# 12_FPGA_banks_3A_3B_4A.net
KiCad netlist of a schematic drawn in Altium Designer
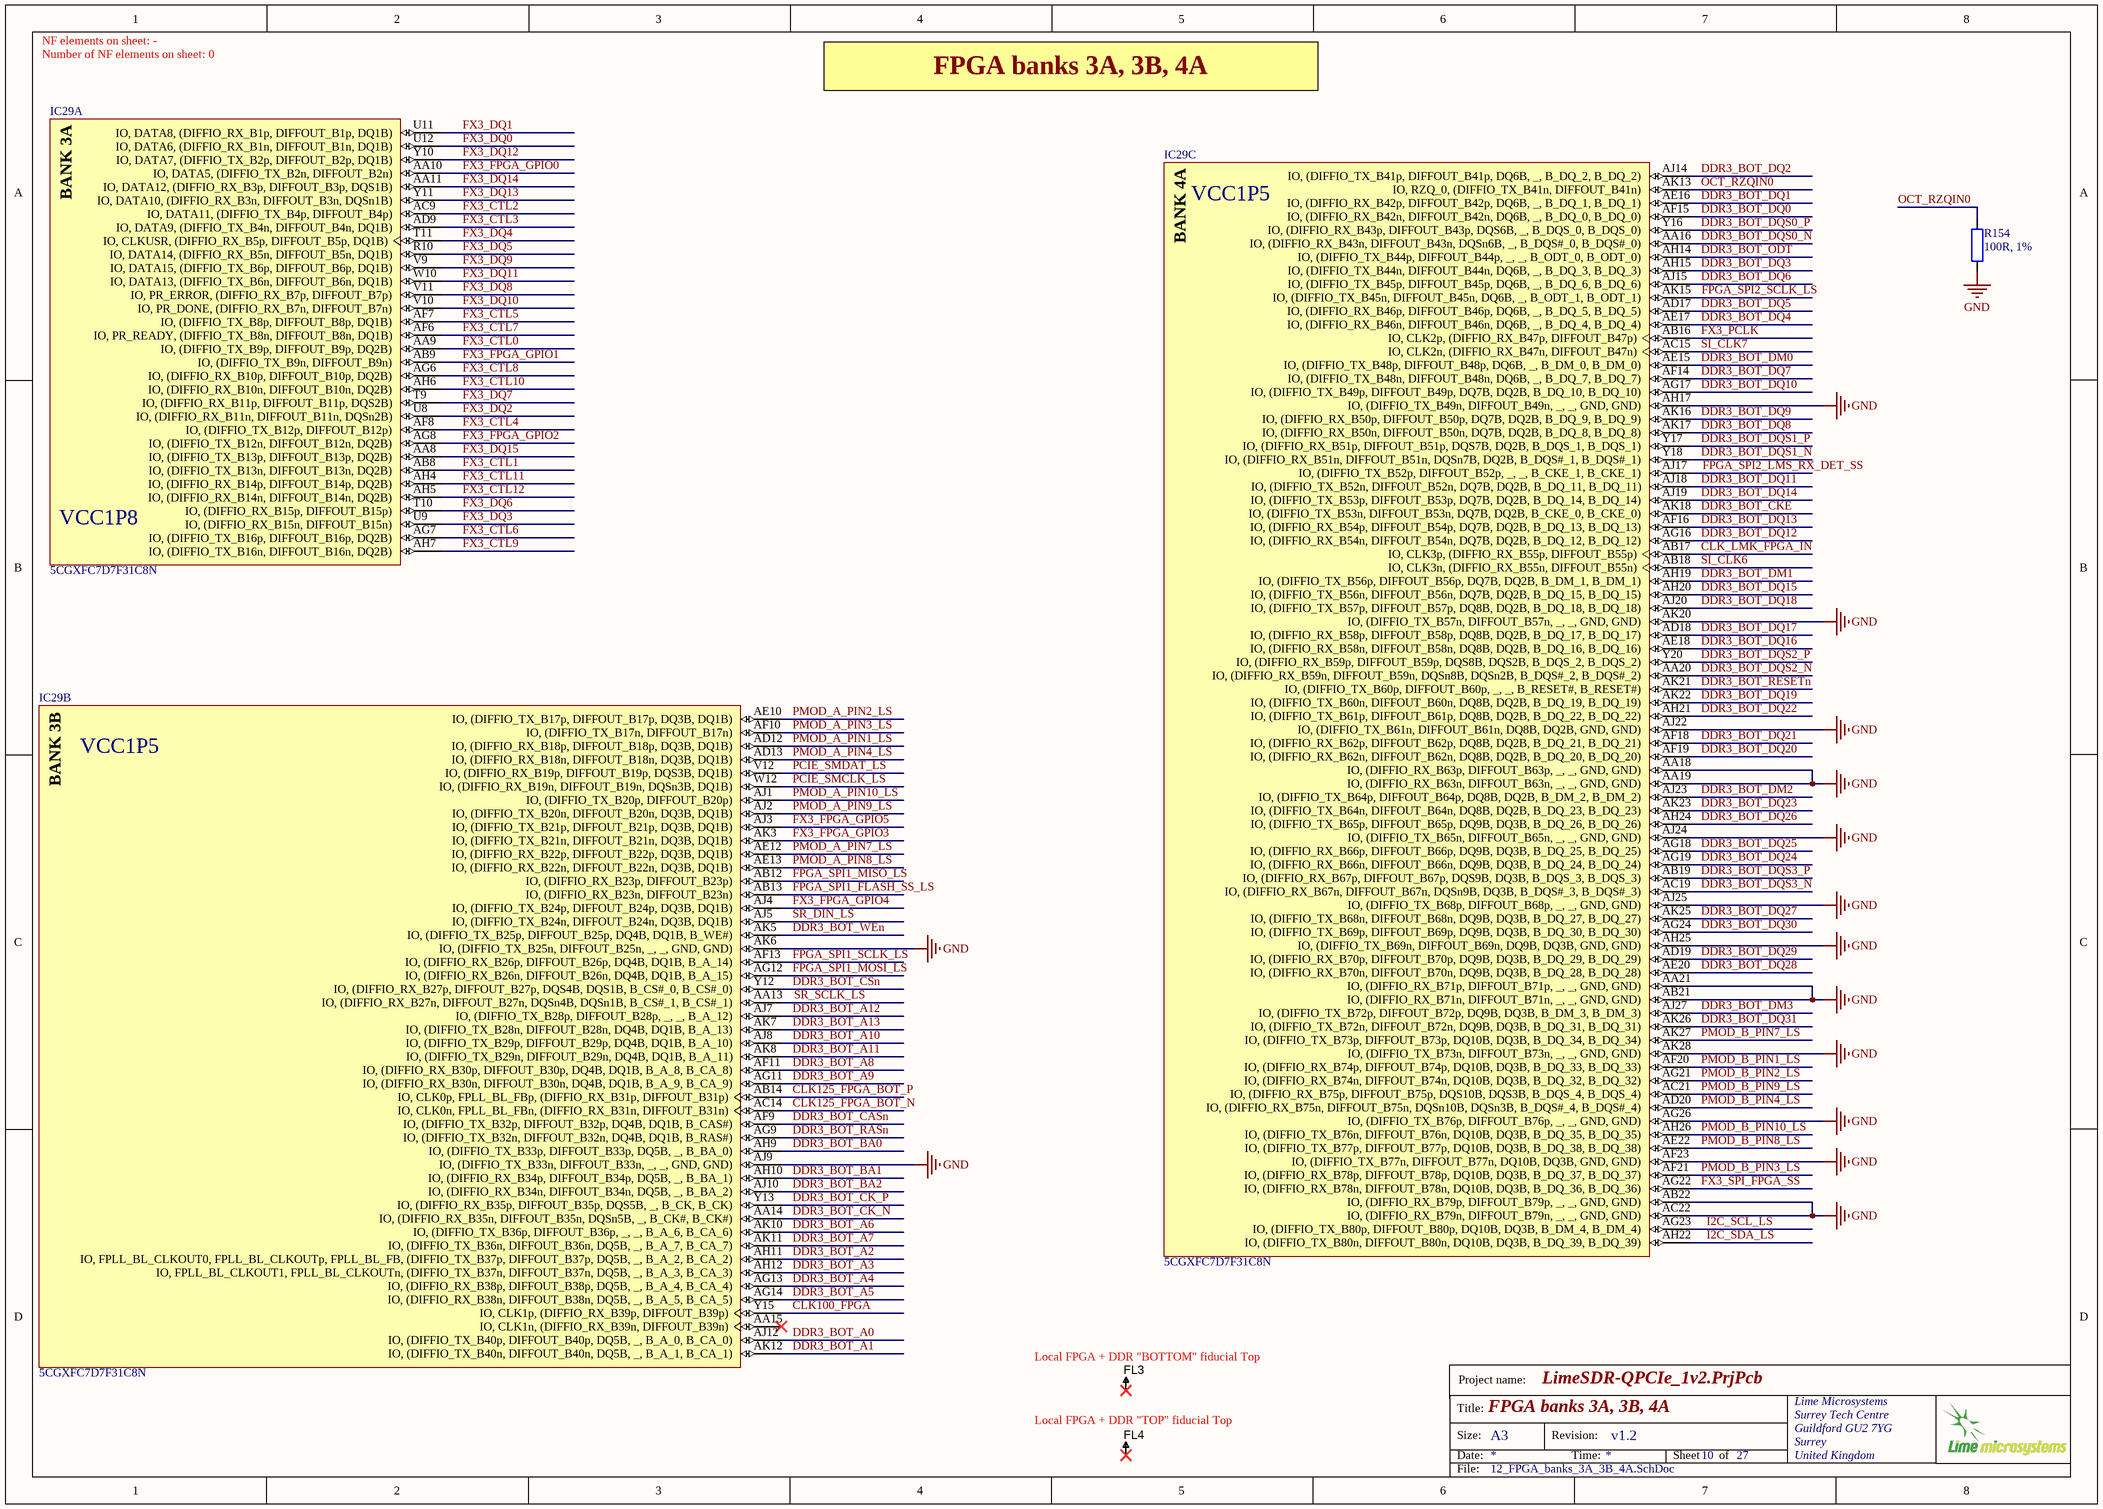
[diagram p0: 12_FPGA_banks_3A_3B_4A.SchDoc]

(export (version "E")
  (design (tool "Eeschema 10.0.6"))
  (components
    (comp (ref "FL3")
      (value "Fiducial")
      (footprint "Fiducial_local")
      (libsource (lib "LimeMicroAltiumLib_schLib") (part "Fiducial"))
    )
    (comp (ref "FL4")
      (value "Fiducial")
      (footprint "Fiducial_local")
      (libsource (lib "LimeMicroAltiumLib_schLib") (part "Fiducial"))
    )
    (comp (ref "IC29")
      (value "5CGXFC7D7F31C8N")
      (footprint "ALTR-FBGA896_A-200")
      (fields (field (name "MANUFACTURER") "Altera"))
      (libsource (lib "LimeMicroAltiumLib_schLib") (part "5CGXFC7D7F31C8N"))
    )
    (comp (ref "R154")
      (value "100R, 1%")
      (footprint "RES0402")
      (fields (field (name "TOLERANCE") "±1%") (field (name "MANUFACTURER") "Stackpole Electronics Inc."))
      (libsource (lib "LimeFPGAboard_schLib") (part "Res_0402"))
    )
  )
  (nets
    (net (code "1") (name "/CLK100_FPGA") (class "Default")
      (node (ref "IC29") (pin "Y15") (pinfunction "IO,_CLK1p,_(DIFFIO_RX_B39p,_DIFFOUT_B39p)_Y15") (pintype "bidirectional"))
    )
    (net (code "2") (name "/CLK125_FPGA_BOT_N") (class "Default")
      (node (ref "IC29") (pin "AC14") (pinfunction "IO,_CLK0n,_FPLL_BL_FBn,_(DIFFIO_RX_B31n,_DIFFOUT_B31n)_AC14") (pintype "bidirectional"))
    )
    (net (code "3") (name "/CLK125_FPGA_BOT_P") (class "Default")
      (node (ref "IC29") (pin "AB14") (pinfunction "IO,_CLK0p,_FPLL_BL_FBp,_(DIFFIO_RX_B31p,_DIFFOUT_B31p)_AB14") (pintype "bidirectional"))
    )
    (net (code "4") (name "/CLK_LMK_FPGA_IN") (class "Default")
      (node (ref "IC29") (pin "AB17") (pinfunction "IO,_CLK3p,_(DIFFIO_RX_B55p,_DIFFOUT_B55p)_AB17") (pintype "bidirectional"))
    )
    (net (code "5") (name "/DDR3_BOT_A0") (class "Default")
      (node (ref "IC29") (pin "AJ12") (pinfunction "IO,_(DIFFIO_TX_B40p,_DIFFOUT_B40p,_DQ5B,__,_B_A_0,_B_CA_0)_AJ12") (pintype "bidirectional"))
    )
    (net (code "6") (name "/DDR3_BOT_A1") (class "Default")
      (node (ref "IC29") (pin "AK12") (pinfunction "IO,_(DIFFIO_TX_B40n,_DIFFOUT_B40n,_DQ5B,__,_B_A_1,_B_CA_1)_AK12") (pintype "bidirectional"))
    )
    (net (code "7") (name "/DDR3_BOT_A2") (class "Default")
      (node (ref "IC29") (pin "AH11") (pinfunction "IO,_FPLL_BL_CLKOUT0,_FPLL_BL_CLKOUTp,_FPLL_BL_FB,_(DIFFIO_TX_B37p,_DIFFOUT_B37p,_DQ5B,__,_B_A_2,_B_CA_2)_AH11") (pintype "bidirectional"))
    )
    (net (code "8") (name "/DDR3_BOT_A3") (class "Default")
      (node (ref "IC29") (pin "AH12") (pinfunction "IO,_FPLL_BL_CLKOUT1,_FPLL_BL_CLKOUTn,_(DIFFIO_TX_B37n,_DIFFOUT_B37n,_DQ5B,__,_B_A_3,_B_CA_3)_AH12") (pintype "bidirectional"))
    )
    (net (code "9") (name "/DDR3_BOT_A4") (class "Default")
      (node (ref "IC29") (pin "AG13") (pinfunction "IO,_(DIFFIO_RX_B38p,_DIFFOUT_B38p,_DQ5B,__,_B_A_4,_B_CA_4)_AG13") (pintype "bidirectional"))
    )
    (net (code "10") (name "/DDR3_BOT_A5") (class "Default")
      (node (ref "IC29") (pin "AG14") (pinfunction "IO,_(DIFFIO_RX_B38n,_DIFFOUT_B38n,_DQ5B,__,_B_A_5,_B_CA_5)_AG14") (pintype "bidirectional"))
    )
    (net (code "11") (name "/DDR3_BOT_A6") (class "Default")
      (node (ref "IC29") (pin "AK10") (pinfunction "IO,_(DIFFIO_TX_B36p,_DIFFOUT_B36p,__,__,_B_A_6,_B_CA_6)_AK10") (pintype "bidirectional"))
    )
    (net (code "12") (name "/DDR3_BOT_A7") (class "Default")
      (node (ref "IC29") (pin "AK11") (pinfunction "IO,_(DIFFIO_TX_B36n,_DIFFOUT_B36n,_DQ5B,__,_B_A_7,_B_CA_7)_AK11") (pintype "bidirectional"))
    )
    (net (code "13") (name "/DDR3_BOT_A8") (class "Default")
      (node (ref "IC29") (pin "AF11") (pinfunction "IO,_(DIFFIO_RX_B30p,_DIFFOUT_B30p,_DQ4B,_DQ1B,_B_A_8,_B_CA_8)_AF11") (pintype "bidirectional"))
    )
    (net (code "14") (name "/DDR3_BOT_A9") (class "Default")
      (node (ref "IC29") (pin "AG11") (pinfunction "IO,_(DIFFIO_RX_B30n,_DIFFOUT_B30n,_DQ4B,_DQ1B,_B_A_9,_B_CA_9)_AG11") (pintype "bidirectional"))
    )
    (net (code "15") (name "/DDR3_BOT_A10") (class "Default")
      (node (ref "IC29") (pin "AJ8") (pinfunction "IO,_(DIFFIO_TX_B29p,_DIFFOUT_B29p,_DQ4B,_DQ1B,_B_A_10)_AJ8") (pintype "bidirectional"))
    )
    (net (code "16") (name "/DDR3_BOT_A11") (class "Default")
      (node (ref "IC29") (pin "AK8") (pinfunction "IO,_(DIFFIO_TX_B29n,_DIFFOUT_B29n,_DQ4B,_DQ1B,_B_A_11)_AK8") (pintype "bidirectional"))
    )
    (net (code "17") (name "/DDR3_BOT_A12") (class "Default")
      (node (ref "IC29") (pin "AJ7") (pinfunction "IO,_(DIFFIO_TX_B28p,_DIFFOUT_B28p,__,__,_B_A_12)_AJ7") (pintype "bidirectional"))
    )
    (net (code "18") (name "/DDR3_BOT_A13") (class "Default")
      (node (ref "IC29") (pin "AK7") (pinfunction "IO,_(DIFFIO_TX_B28n,_DIFFOUT_B28n,_DQ4B,_DQ1B,_B_A_13)_AK7") (pintype "bidirectional"))
    )
    (net (code "19") (name "/DDR3_BOT_BA0") (class "Default")
      (node (ref "IC29") (pin "AH9") (pinfunction "IO,_(DIFFIO_TX_B33p,_DIFFOUT_B33p,_DQ5B,__,_B_BA_0)_AH9") (pintype "bidirectional"))
    )
    (net (code "20") (name "/DDR3_BOT_BA1") (class "Default")
      (node (ref "IC29") (pin "AH10") (pinfunction "IO,_(DIFFIO_RX_B34p,_DIFFOUT_B34p,_DQ5B,__,_B_BA_1)_AH10") (pintype "bidirectional"))
    )
    (net (code "21") (name "/DDR3_BOT_BA2") (class "Default")
      (node (ref "IC29") (pin "AJ10") (pinfunction "IO,_(DIFFIO_RX_B34n,_DIFFOUT_B34n,_DQ5B,__,_B_BA_2)_AJ10") (pintype "bidirectional"))
    )
    (net (code "22") (name "/DDR3_BOT_CASn") (class "Default")
      (node (ref "IC29") (pin "AF9") (pinfunction "IO,_(DIFFIO_TX_B32p,_DIFFOUT_B32p,_DQ4B,_DQ1B,_B_CAS#)_AF9") (pintype "bidirectional"))
    )
    (net (code "23") (name "/DDR3_BOT_CKE") (class "Default")
      (node (ref "IC29") (pin "AK18") (pinfunction "IO,_(DIFFIO_TX_B53n,_DIFFOUT_B53n,_DQ7B,_DQ2B,_B_CKE_0,_B_CKE_0)_AK18") (pintype "bidirectional"))
    )
    (net (code "24") (name "/DDR3_BOT_CK_N") (class "Default")
      (node (ref "IC29") (pin "AA14") (pinfunction "IO,_(DIFFIO_RX_B35n,_DIFFOUT_B35n,_DQSn5B,__,_B_CK#,_B_CK#)_AA14") (pintype "bidirectional"))
    )
    (net (code "25") (name "/DDR3_BOT_CK_P") (class "Default")
      (node (ref "IC29") (pin "Y13") (pinfunction "IO,_(DIFFIO_RX_B35p,_DIFFOUT_B35p,_DQS5B,__,_B_CK,_B_CK)_Y13") (pintype "bidirectional"))
    )
    (net (code "26") (name "/DDR3_BOT_CSn") (class "Default")
      (node (ref "IC29") (pin "Y12") (pinfunction "IO,_(DIFFIO_RX_B27p,_DIFFOUT_B27p,_DQS4B,_DQS1B,_B_CS#_0,_B_CS#_0)_Y12") (pintype "bidirectional"))
    )
    (net (code "27") (name "/DDR3_BOT_DM0") (class "Default")
      (node (ref "IC29") (pin "AE15") (pinfunction "IO,_(DIFFIO_TX_B48p,_DIFFOUT_B48p,_DQ6B,__,_B_DM_0,_B_DM_0)_AE15") (pintype "bidirectional"))
    )
    (net (code "28") (name "/DDR3_BOT_DM1") (class "Default")
      (node (ref "IC29") (pin "AH19") (pinfunction "IO,_(DIFFIO_TX_B56p,_DIFFOUT_B56p,_DQ7B,_DQ2B,_B_DM_1,_B_DM_1)_AH19") (pintype "bidirectional"))
    )
    (net (code "29") (name "/DDR3_BOT_DM2") (class "Default")
      (node (ref "IC29") (pin "AJ23") (pinfunction "IO,_(DIFFIO_TX_B64p,_DIFFOUT_B64p,_DQ8B,_DQ2B,_B_DM_2,_B_DM_2)_AJ23") (pintype "bidirectional"))
    )
    (net (code "30") (name "/DDR3_BOT_DM3") (class "Default")
      (node (ref "IC29") (pin "AJ27") (pinfunction "IO,_(DIFFIO_TX_B72p,_DIFFOUT_B72p,_DQ9B,_DQ3B,_B_DM_3,_B_DM_3)_AJ27") (pintype "bidirectional"))
    )
    (net (code "31") (name "/DDR3_BOT_DQ0") (class "Default")
      (node (ref "IC29") (pin "AF15") (pinfunction "IO,_(DIFFIO_RX_B42n,_DIFFOUT_B42n,_DQ6B,__,_B_DQ_0,_B_DQ_0)_AF15") (pintype "bidirectional"))
    )
    (net (code "32") (name "/DDR3_BOT_DQ1") (class "Default")
      (node (ref "IC29") (pin "AE16") (pinfunction "IO,_(DIFFIO_RX_B42p,_DIFFOUT_B42p,_DQ6B,__,_B_DQ_1,_B_DQ_1)_AE16") (pintype "bidirectional"))
    )
    (net (code "33") (name "/DDR3_BOT_DQ2") (class "Default")
      (node (ref "IC29") (pin "AJ14") (pinfunction "IO,_(DIFFIO_TX_B41p,_DIFFOUT_B41p,_DQ6B,__,_B_DQ_2,_B_DQ_2)_AJ14") (pintype "bidirectional"))
    )
    (net (code "34") (name "/DDR3_BOT_DQ3") (class "Default")
      (node (ref "IC29") (pin "AH15") (pinfunction "IO,_(DIFFIO_TX_B44n,_DIFFOUT_B44n,_DQ6B,__,_B_DQ_3,_B_DQ_3)_AH15") (pintype "bidirectional"))
    )
    (net (code "35") (name "/DDR3_BOT_DQ4") (class "Default")
      (node (ref "IC29") (pin "AE17") (pinfunction "IO,_(DIFFIO_RX_B46n,_DIFFOUT_B46n,_DQ6B,__,_B_DQ_4,_B_DQ_4)_AE17") (pintype "bidirectional"))
    )
    (net (code "36") (name "/DDR3_BOT_DQ5") (class "Default")
      (node (ref "IC29") (pin "AD17") (pinfunction "IO,_(DIFFIO_RX_B46p,_DIFFOUT_B46p,_DQ6B,__,_B_DQ_5,_B_DQ_5)_AD17") (pintype "bidirectional"))
    )
    (net (code "37") (name "/DDR3_BOT_DQ6") (class "Default")
      (node (ref "IC29") (pin "AJ15") (pinfunction "IO,_(DIFFIO_TX_B45p,_DIFFOUT_B45p,_DQ6B,__,_B_DQ_6,_B_DQ_6)_AJ15") (pintype "bidirectional"))
    )
    (net (code "38") (name "/DDR3_BOT_DQ7") (class "Default")
      (node (ref "IC29") (pin "AF14") (pinfunction "IO,_(DIFFIO_TX_B48n,_DIFFOUT_B48n,_DQ6B,__,_B_DQ_7,_B_DQ_7)_AF14") (pintype "bidirectional"))
    )
    (net (code "39") (name "/DDR3_BOT_DQ8") (class "Default")
      (node (ref "IC29") (pin "AK17") (pinfunction "IO,_(DIFFIO_RX_B50n,_DIFFOUT_B50n,_DQ7B,_DQ2B,_B_DQ_8,_B_DQ_8)_AK17") (pintype "bidirectional"))
    )
    (net (code "40") (name "/DDR3_BOT_DQ9") (class "Default")
      (node (ref "IC29") (pin "AK16") (pinfunction "IO,_(DIFFIO_RX_B50p,_DIFFOUT_B50p,_DQ7B,_DQ2B,_B_DQ_9,_B_DQ_9)_AK16") (pintype "bidirectional"))
    )
    (net (code "41") (name "/DDR3_BOT_DQ10") (class "Default")
      (node (ref "IC29") (pin "AG17") (pinfunction "IO,_(DIFFIO_TX_B49p,_DIFFOUT_B49p,_DQ7B,_DQ2B,_B_DQ_10,_B_DQ_10)_AG17") (pintype "bidirectional"))
    )
    (net (code "42") (name "/DDR3_BOT_DQ11") (class "Default")
      (node (ref "IC29") (pin "AJ18") (pinfunction "IO,_(DIFFIO_TX_B52n,_DIFFOUT_B52n,_DQ7B,_DQ2B,_B_DQ_11,_B_DQ_11)_AJ18") (pintype "bidirectional"))
    )
    (net (code "43") (name "/DDR3_BOT_DQ12") (class "Default")
      (node (ref "IC29") (pin "AG16") (pinfunction "IO,_(DIFFIO_RX_B54n,_DIFFOUT_B54n,_DQ7B,_DQ2B,_B_DQ_12,_B_DQ_12)_AG16") (pintype "bidirectional"))
    )
    (net (code "44") (name "/DDR3_BOT_DQ13") (class "Default")
      (node (ref "IC29") (pin "AF16") (pinfunction "IO,_(DIFFIO_RX_B54p,_DIFFOUT_B54p,_DQ7B,_DQ2B,_B_DQ_13,_B_DQ_13)_AF16") (pintype "bidirectional"))
    )
    (net (code "45") (name "/DDR3_BOT_DQ14") (class "Default")
      (node (ref "IC29") (pin "AJ19") (pinfunction "IO,_(DIFFIO_TX_B53p,_DIFFOUT_B53p,_DQ7B,_DQ2B,_B_DQ_14,_B_DQ_14)_AJ19") (pintype "bidirectional"))
    )
    (net (code "46") (name "/DDR3_BOT_DQ15") (class "Default")
      (node (ref "IC29") (pin "AH20") (pinfunction "IO,_(DIFFIO_TX_B56n,_DIFFOUT_B56n,_DQ7B,_DQ2B,_B_DQ_15,_B_DQ_15)_AH20") (pintype "bidirectional"))
    )
    (net (code "47") (name "/DDR3_BOT_DQ16") (class "Default")
      (node (ref "IC29") (pin "AE18") (pinfunction "IO,_(DIFFIO_RX_B58n,_DIFFOUT_B58n,_DQ8B,_DQ2B,_B_DQ_16,_B_DQ_16)_AE18") (pintype "bidirectional"))
    )
    (net (code "48") (name "/DDR3_BOT_DQ17") (class "Default")
      (node (ref "IC29") (pin "AD18") (pinfunction "IO,_(DIFFIO_RX_B58p,_DIFFOUT_B58p,_DQ8B,_DQ2B,_B_DQ_17,_B_DQ_17)_AD18") (pintype "bidirectional"))
    )
    (net (code "49") (name "/DDR3_BOT_DQ18") (class "Default")
      (node (ref "IC29") (pin "AJ20") (pinfunction "IO,_(DIFFIO_TX_B57p,_DIFFOUT_B57p,_DQ8B,_DQ2B,_B_DQ_18,_B_DQ_18)_AJ20") (pintype "bidirectional"))
    )
    (net (code "50") (name "/DDR3_BOT_DQ19") (class "Default")
      (node (ref "IC29") (pin "AK22") (pinfunction "IO,_(DIFFIO_TX_B60n,_DIFFOUT_B60n,_DQ8B,_DQ2B,_B_DQ_19,_B_DQ_19)_AK22") (pintype "bidirectional"))
    )
    (net (code "51") (name "/DDR3_BOT_DQ20") (class "Default")
      (node (ref "IC29") (pin "AF19") (pinfunction "IO,_(DIFFIO_RX_B62n,_DIFFOUT_B62n,_DQ8B,_DQ2B,_B_DQ_20,_B_DQ_20)_AF19") (pintype "bidirectional"))
    )
    (net (code "52") (name "/DDR3_BOT_DQ21") (class "Default")
      (node (ref "IC29") (pin "AF18") (pinfunction "IO,_(DIFFIO_RX_B62p,_DIFFOUT_B62p,_DQ8B,_DQ2B,_B_DQ_21,_B_DQ_21)_AF18") (pintype "bidirectional"))
    )
    (net (code "53") (name "/DDR3_BOT_DQ22") (class "Default")
      (node (ref "IC29") (pin "AH21") (pinfunction "IO,_(DIFFIO_TX_B61p,_DIFFOUT_B61p,_DQ8B,_DQ2B,_B_DQ_22,_B_DQ_22)_AH21") (pintype "bidirectional"))
    )
    (net (code "54") (name "/DDR3_BOT_DQ23") (class "Default")
      (node (ref "IC29") (pin "AK23") (pinfunction "IO,_(DIFFIO_TX_B64n,_DIFFOUT_B64n,_DQ8B,_DQ2B,_B_DQ_23,_B_DQ_23)_AK23") (pintype "bidirectional"))
    )
    (net (code "55") (name "/DDR3_BOT_DQ24") (class "Default")
      (node (ref "IC29") (pin "AG19") (pinfunction "IO,_(DIFFIO_RX_B66n,_DIFFOUT_B66n,_DQ9B,_DQ3B,_B_DQ_24,_B_DQ_24)_AG19") (pintype "bidirectional"))
    )
    (net (code "56") (name "/DDR3_BOT_DQ25") (class "Default")
      (node (ref "IC29") (pin "AG18") (pinfunction "IO,_(DIFFIO_RX_B66p,_DIFFOUT_B66p,_DQ9B,_DQ3B,_B_DQ_25,_B_DQ_25)_AG18") (pintype "bidirectional"))
    )
    (net (code "57") (name "/DDR3_BOT_DQ26") (class "Default")
      (node (ref "IC29") (pin "AH24") (pinfunction "IO,_(DIFFIO_TX_B65p,_DIFFOUT_B65p,_DQ9B,_DQ3B,_B_DQ_26,_B_DQ_26)_AH24") (pintype "bidirectional"))
    )
    (net (code "58") (name "/DDR3_BOT_DQ27") (class "Default")
      (node (ref "IC29") (pin "AK25") (pinfunction "IO,_(DIFFIO_TX_B68n,_DIFFOUT_B68n,_DQ9B,_DQ3B,_B_DQ_27,_B_DQ_27)_AK25") (pintype "bidirectional"))
    )
    (net (code "59") (name "/DDR3_BOT_DQ28") (class "Default")
      (node (ref "IC29") (pin "AE20") (pinfunction "IO,_(DIFFIO_RX_B70n,_DIFFOUT_B70n,_DQ9B,_DQ3B,_B_DQ_28,_B_DQ_28)_AE20") (pintype "bidirectional"))
    )
    (net (code "60") (name "/DDR3_BOT_DQ29") (class "Default")
      (node (ref "IC29") (pin "AD19") (pinfunction "IO,_(DIFFIO_RX_B70p,_DIFFOUT_B70p,_DQ9B,_DQ3B,_B_DQ_29,_B_DQ_29)_AD19") (pintype "bidirectional"))
    )
    (net (code "61") (name "/DDR3_BOT_DQ30") (class "Default")
      (node (ref "IC29") (pin "AG24") (pinfunction "IO,_(DIFFIO_TX_B69p,_DIFFOUT_B69p,_DQ9B,_DQ3B,_B_DQ_30,_B_DQ_30)_AG24") (pintype "bidirectional"))
    )
    (net (code "62") (name "/DDR3_BOT_DQ31") (class "Default")
      (node (ref "IC29") (pin "AK26") (pinfunction "IO,_(DIFFIO_TX_B72n,_DIFFOUT_B72n,_DQ9B,_DQ3B,_B_DQ_31,_B_DQ_31)_AK26") (pintype "bidirectional"))
    )
    (net (code "63") (name "/DDR3_BOT_DQS0_N") (class "Default")
      (node (ref "IC29") (pin "AA16") (pinfunction "IO,_(DIFFIO_RX_B43n,_DIFFOUT_B43n,_DQSn6B,__,_B_DQS#_0,_B_DQS#_0)_AA16") (pintype "bidirectional"))
    )
    (net (code "64") (name "/DDR3_BOT_DQS0_P") (class "Default")
      (node (ref "IC29") (pin "Y16") (pinfunction "IO,_(DIFFIO_RX_B43p,_DIFFOUT_B43p,_DQS6B,__,_B_DQS_0,_B_DQS_0)_Y16") (pintype "bidirectional"))
    )
    (net (code "65") (name "/DDR3_BOT_DQS1_N") (class "Default")
      (node (ref "IC29") (pin "Y18") (pinfunction "IO,_(DIFFIO_RX_B51n,_DIFFOUT_B51n,_DQSn7B,_DQ2B,_B_DQS#_1,_B_DQS#_1)_Y18") (pintype "bidirectional"))
    )
    (net (code "66") (name "/DDR3_BOT_DQS1_P") (class "Default")
      (node (ref "IC29") (pin "Y17") (pinfunction "IO,_(DIFFIO_RX_B51p,_DIFFOUT_B51p,_DQS7B,_DQ2B,_B_DQS_1,_B_DQS_1)_Y17") (pintype "bidirectional"))
    )
    (net (code "67") (name "/DDR3_BOT_DQS2_N") (class "Default")
      (node (ref "IC29") (pin "AA20") (pinfunction "IO,_(DIFFIO_RX_B59n,_DIFFOUT_B59n,_DQSn8B,_DQSn2B,_B_DQS#_2,_B_DQS#_2)_AA20") (pintype "bidirectional"))
    )
    (net (code "68") (name "/DDR3_BOT_DQS2_P") (class "Default")
      (node (ref "IC29") (pin "Y20") (pinfunction "IO,_(DIFFIO_RX_B59p,_DIFFOUT_B59p,_DQS8B,_DQS2B,_B_DQS_2,_B_DQS_2)_Y20") (pintype "bidirectional"))
    )
    (net (code "69") (name "/DDR3_BOT_DQS3_N") (class "Default")
      (node (ref "IC29") (pin "AC19") (pinfunction "IO,_(DIFFIO_RX_B67n,_DIFFOUT_B67n,_DQSn9B,_DQ3B,_B_DQS#_3,_B_DQS#_3)_AC19") (pintype "bidirectional"))
    )
    (net (code "70") (name "/DDR3_BOT_DQS3_P") (class "Default")
      (node (ref "IC29") (pin "AB19") (pinfunction "IO,_(DIFFIO_RX_B67p,_DIFFOUT_B67p,_DQS9B,_DQ3B,_B_DQS_3,_B_DQS_3)_AB19") (pintype "bidirectional"))
    )
    (net (code "71") (name "/DDR3_BOT_ODT") (class "Default")
      (node (ref "IC29") (pin "AH14") (pinfunction "IO,_(DIFFIO_TX_B44p,_DIFFOUT_B44p,__,__,_B_ODT_0,_B_ODT_0)_AH14") (pintype "bidirectional"))
    )
    (net (code "72") (name "/DDR3_BOT_RASn") (class "Default")
      (node (ref "IC29") (pin "AG9") (pinfunction "IO,_(DIFFIO_TX_B32n,_DIFFOUT_B32n,_DQ4B,_DQ1B,_B_RAS#)_AG9") (pintype "bidirectional"))
    )
    (net (code "73") (name "/DDR3_BOT_RESETn") (class "Default")
      (node (ref "IC29") (pin "AK21") (pinfunction "IO,_(DIFFIO_TX_B60p,_DIFFOUT_B60p,__,__,_B_RESET#,_B_RESET#)_AK21") (pintype "bidirectional"))
    )
    (net (code "74") (name "/DDR3_BOT_WEn") (class "Default")
      (node (ref "IC29") (pin "AK5") (pinfunction "IO,_(DIFFIO_TX_B25p,_DIFFOUT_B25p,_DQ4B,_DQ1B,_B_WE#)_AK5") (pintype "bidirectional"))
    )
    (net (code "75") (name "/FPGA_SPI1_FLASH_SS_LS") (class "Default")
      (node (ref "IC29") (pin "AB13") (pinfunction "IO,_(DIFFIO_RX_B23n,_DIFFOUT_B23n)_AB13") (pintype "bidirectional"))
    )
    (net (code "76") (name "/FPGA_SPI1_MISO_LS") (class "Default")
      (node (ref "IC29") (pin "AB12") (pinfunction "IO,_(DIFFIO_RX_B23p,_DIFFOUT_B23p)_AB12") (pintype "bidirectional"))
    )
    (net (code "77") (name "/FPGA_SPI1_MOSI_LS") (class "Default")
      (node (ref "IC29") (pin "AG12") (pinfunction "IO,_(DIFFIO_RX_B26n,_DIFFOUT_B26n,_DQ4B,_DQ1B,_B_A_15)_AG12") (pintype "bidirectional"))
    )
    (net (code "78") (name "/FPGA_SPI1_SCLK_LS") (class "Default")
      (node (ref "IC29") (pin "AF13") (pinfunction "IO,_(DIFFIO_RX_B26p,_DIFFOUT_B26p,_DQ4B,_DQ1B,_B_A_14)_AF13") (pintype "bidirectional"))
    )
    (net (code "79") (name "/FPGA_SPI2_LMS_RX_DET_SS") (class "Default")
      (node (ref "IC29") (pin "AJ17") (pinfunction "IO,_(DIFFIO_TX_B52p,_DIFFOUT_B52p,__,__,_B_CKE_1,_B_CKE_1)_AJ17") (pintype "bidirectional"))
    )
    (net (code "80") (name "/FPGA_SPI2_SCLK_LS") (class "Default")
      (node (ref "IC29") (pin "AK15") (pinfunction "IO,_(DIFFIO_TX_B45n,_DIFFOUT_B45n,_DQ6B,__,_B_ODT_1,_B_ODT_1)_AK15") (pintype "bidirectional"))
    )
    (net (code "81") (name "/FX3_CTL0") (class "Default")
      (node (ref "IC29") (pin "AA9") (pinfunction "IO,_(DIFFIO_TX_B9p,_DIFFOUT_B9p,_DQ2B)_AA9") (pintype "bidirectional"))
    )
    (net (code "82") (name "/FX3_CTL1") (class "Default")
      (node (ref "IC29") (pin "AB8") (pinfunction "IO,_(DIFFIO_TX_B13n,_DIFFOUT_B13n,_DQ2B)_AB8") (pintype "bidirectional"))
    )
    (net (code "83") (name "/FX3_CTL2") (class "Default")
      (node (ref "IC29") (pin "AC9") (pinfunction "IO,_DATA11,_(DIFFIO_TX_B4p,_DIFFOUT_B4p)_AC9") (pintype "bidirectional"))
    )
    (net (code "84") (name "/FX3_CTL3") (class "Default")
      (node (ref "IC29") (pin "AD9") (pinfunction "IO,_DATA9,_(DIFFIO_TX_B4n,_DIFFOUT_B4n,_DQ1B)_AD9") (pintype "bidirectional"))
    )
    (net (code "85") (name "/FX3_CTL4") (class "Default")
      (node (ref "IC29") (pin "AF8") (pinfunction "IO,_(DIFFIO_TX_B12p,_DIFFOUT_B12p)_AF8") (pintype "bidirectional"))
    )
    (net (code "86") (name "/FX3_CTL5") (class "Default")
      (node (ref "IC29") (pin "AF7") (pinfunction "IO,_(DIFFIO_TX_B8p,_DIFFOUT_B8p,_DQ1B)_AF7") (pintype "bidirectional"))
    )
    (net (code "87") (name "/FX3_CTL6") (class "Default")
      (node (ref "IC29") (pin "AG7") (pinfunction "IO,_(DIFFIO_TX_B16p,_DIFFOUT_B16p,_DQ2B)_AG7") (pintype "bidirectional"))
    )
    (net (code "88") (name "/FX3_CTL7") (class "Default")
      (node (ref "IC29") (pin "AF6") (pinfunction "IO,_PR_READY,_(DIFFIO_TX_B8n,_DIFFOUT_B8n,_DQ1B)_AF6") (pintype "bidirectional"))
    )
    (net (code "89") (name "/FX3_CTL8") (class "Default")
      (node (ref "IC29") (pin "AG6") (pinfunction "IO,_(DIFFIO_RX_B10p,_DIFFOUT_B10p,_DQ2B)_AG6") (pintype "bidirectional"))
    )
    (net (code "90") (name "/FX3_CTL9") (class "Default")
      (node (ref "IC29") (pin "AH7") (pinfunction "IO,_(DIFFIO_TX_B16n,_DIFFOUT_B16n,_DQ2B)_AH7") (pintype "bidirectional"))
    )
    (net (code "91") (name "/FX3_CTL10") (class "Default")
      (node (ref "IC29") (pin "AH6") (pinfunction "IO,_(DIFFIO_RX_B10n,_DIFFOUT_B10n,_DQ2B)_AH6") (pintype "bidirectional"))
    )
    (net (code "92") (name "/FX3_CTL11") (class "Default")
      (node (ref "IC29") (pin "AH4") (pinfunction "IO,_(DIFFIO_RX_B14p,_DIFFOUT_B14p,_DQ2B)_AH4") (pintype "bidirectional"))
    )
    (net (code "93") (name "/FX3_CTL12") (class "Default")
      (node (ref "IC29") (pin "AH5") (pinfunction "IO,_(DIFFIO_RX_B14n,_DIFFOUT_B14n,_DQ2B)_AH5") (pintype "bidirectional"))
    )
    (net (code "94") (name "/FX3_DQ0") (class "Default")
      (node (ref "IC29") (pin "U12") (pinfunction "IO,_DATA6,_(DIFFIO_RX_B1n,_DIFFOUT_B1n,_DQ1B)_U12") (pintype "bidirectional"))
    )
    (net (code "95") (name "/FX3_DQ1") (class "Default")
      (node (ref "IC29") (pin "U11") (pinfunction "IO,_DATA8,_(DIFFIO_RX_B1p,_DIFFOUT_B1p,_DQ1B)_U11") (pintype "bidirectional"))
    )
    (net (code "96") (name "/FX3_DQ2") (class "Default")
      (node (ref "IC29") (pin "U8") (pinfunction "IO,_(DIFFIO_RX_B11n,_DIFFOUT_B11n,_DQSn2B)_U8") (pintype "bidirectional"))
    )
    (net (code "97") (name "/FX3_DQ3") (class "Default")
      (node (ref "IC29") (pin "U9") (pinfunction "IO,_(DIFFIO_RX_B15n,_DIFFOUT_B15n)_U9") (pintype "bidirectional"))
    )
    (net (code "98") (name "/FX3_DQ4") (class "Default")
      (node (ref "IC29") (pin "T11") (pinfunction "IO,_CLKUSR,_(DIFFIO_RX_B5p,_DIFFOUT_B5p,_DQ1B)_T11") (pintype "bidirectional"))
    )
    (net (code "99") (name "/FX3_DQ5") (class "Default")
      (node (ref "IC29") (pin "R10") (pinfunction "IO,_DATA14,_(DIFFIO_RX_B5n,_DIFFOUT_B5n,_DQ1B)_R10") (pintype "bidirectional"))
    )
    (net (code "100") (name "/FX3_DQ6") (class "Default")
      (node (ref "IC29") (pin "T10") (pinfunction "IO,_(DIFFIO_RX_B15p,_DIFFOUT_B15p)_T10") (pintype "bidirectional"))
    )
    (net (code "101") (name "/FX3_DQ7") (class "Default")
      (node (ref "IC29") (pin "T9") (pinfunction "IO,_(DIFFIO_RX_B11p,_DIFFOUT_B11p,_DQS2B)_T9") (pintype "bidirectional"))
    )
    (net (code "102") (name "/FX3_DQ8") (class "Default")
      (node (ref "IC29") (pin "V11") (pinfunction "IO,_PR_ERROR,_(DIFFIO_RX_B7p,_DIFFOUT_B7p)_V11") (pintype "bidirectional"))
    )
    (net (code "103") (name "/FX3_DQ9") (class "Default")
      (node (ref "IC29") (pin "V9") (pinfunction "IO,_DATA15,_(DIFFIO_TX_B6p,_DIFFOUT_B6p,_DQ1B)_V9") (pintype "bidirectional"))
    )
    (net (code "104") (name "/FX3_DQ10") (class "Default")
      (node (ref "IC29") (pin "V10") (pinfunction "IO,_PR_DONE,_(DIFFIO_RX_B7n,_DIFFOUT_B7n)_V10") (pintype "bidirectional"))
    )
    (net (code "105") (name "/FX3_DQ11") (class "Default")
      (node (ref "IC29") (pin "W10") (pinfunction "IO,_DATA13,_(DIFFIO_TX_B6n,_DIFFOUT_B6n,_DQ1B)_W10") (pintype "bidirectional"))
    )
    (net (code "106") (name "/FX3_DQ12") (class "Default")
      (node (ref "IC29") (pin "Y10") (pinfunction "IO,_DATA7,_(DIFFIO_TX_B2p,_DIFFOUT_B2p,_DQ1B)_Y10") (pintype "bidirectional"))
    )
    (net (code "107") (name "/FX3_DQ13") (class "Default")
      (node (ref "IC29") (pin "Y11") (pinfunction "IO,_DATA10,_(DIFFIO_RX_B3n,_DIFFOUT_B3n,_DQSn1B)_Y11") (pintype "bidirectional"))
    )
    (net (code "108") (name "/FX3_DQ14") (class "Default")
      (node (ref "IC29") (pin "AA11") (pinfunction "IO,_DATA12,_(DIFFIO_RX_B3p,_DIFFOUT_B3p,_DQS1B)_AA11") (pintype "bidirectional"))
    )
    (net (code "109") (name "/FX3_DQ15") (class "Default")
      (node (ref "IC29") (pin "AA8") (pinfunction "IO,_(DIFFIO_TX_B13p,_DIFFOUT_B13p,_DQ2B)_AA8") (pintype "bidirectional"))
    )
    (net (code "110") (name "/FX3_FPGA_GPIO0") (class "Default")
      (node (ref "IC29") (pin "AA10") (pinfunction "IO,_DATA5,_(DIFFIO_TX_B2n,_DIFFOUT_B2n)_AA10") (pintype "bidirectional"))
    )
    (net (code "111") (name "/FX3_FPGA_GPIO1") (class "Default")
      (node (ref "IC29") (pin "AB9") (pinfunction "IO,_(DIFFIO_TX_B9n,_DIFFOUT_B9n)_AB9") (pintype "bidirectional"))
    )
    (net (code "112") (name "/FX3_FPGA_GPIO2") (class "Default")
      (node (ref "IC29") (pin "AG8") (pinfunction "IO,_(DIFFIO_TX_B12n,_DIFFOUT_B12n,_DQ2B)_AG8") (pintype "bidirectional"))
    )
    (net (code "113") (name "/FX3_FPGA_GPIO3") (class "Default")
      (node (ref "IC29") (pin "AK3") (pinfunction "IO,_(DIFFIO_TX_B21n,_DIFFOUT_B21n,_DQ3B,_DQ1B)_AK3") (pintype "bidirectional"))
    )
    (net (code "114") (name "/FX3_FPGA_GPIO4") (class "Default")
      (node (ref "IC29") (pin "AJ4") (pinfunction "IO,_(DIFFIO_TX_B24p,_DIFFOUT_B24p,_DQ3B,_DQ1B)_AJ4") (pintype "bidirectional"))
    )
    (net (code "115") (name "/FX3_FPGA_GPIO5") (class "Default")
      (node (ref "IC29") (pin "AJ3") (pinfunction "IO,_(DIFFIO_TX_B21p,_DIFFOUT_B21p,_DQ3B,_DQ1B)_AJ3") (pintype "bidirectional"))
    )
    (net (code "116") (name "/FX3_PCLK") (class "Default")
      (node (ref "IC29") (pin "AB16") (pinfunction "IO,_CLK2p,_(DIFFIO_RX_B47p,_DIFFOUT_B47p)_AB16") (pintype "bidirectional"))
    )
    (net (code "117") (name "/FX3_SPI_FPGA_SS") (class "Default")
      (node (ref "IC29") (pin "AG22") (pinfunction "IO,_(DIFFIO_RX_B78n,_DIFFOUT_B78n,_DQ10B,_DQ3B,_B_DQ_36,_B_DQ_36)_AG22") (pintype "bidirectional"))
    )
    (net (code "118") (name "/I2C_SCL_LS") (class "Default")
      (node (ref "IC29") (pin "AG23") (pinfunction "IO,_(DIFFIO_TX_B80p,_DIFFOUT_B80p,_DQ10B,_DQ3B,_B_DM_4,_B_DM_4)_AG23") (pintype "bidirectional"))
    )
    (net (code "119") (name "/I2C_SDA_LS") (class "Default")
      (node (ref "IC29") (pin "AH22") (pinfunction "IO,_(DIFFIO_TX_B80n,_DIFFOUT_B80n,_DQ10B,_DQ3B,_B_DQ_39,_B_DQ_39)_AH22") (pintype "bidirectional"))
    )
    (net (code "120") (name "/OCT_RZQIN0") (class "Default")
      (node (ref "IC29") (pin "AK13") (pinfunction "IO,_RZQ_0,_(DIFFIO_TX_B41n,_DIFFOUT_B41n)_AK13") (pintype "bidirectional"))
      (node (ref "R154") (pin "2") (pinfunction "2_2") (pintype "passive"))
    )
    (net (code "121") (name "/PCIE_SMCLK_LS") (class "Default")
      (node (ref "IC29") (pin "W12") (pinfunction "IO,_(DIFFIO_RX_B19n,_DIFFOUT_B19n,_DQSn3B,_DQ1B)_W12") (pintype "bidirectional"))
    )
    (net (code "122") (name "/PCIE_SMDAT_LS") (class "Default")
      (node (ref "IC29") (pin "V12") (pinfunction "IO,_(DIFFIO_RX_B19p,_DIFFOUT_B19p,_DQS3B,_DQ1B)_V12") (pintype "bidirectional"))
    )
    (net (code "123") (name "/PMOD_A_PIN1_LS") (class "Default")
      (node (ref "IC29") (pin "AD12") (pinfunction "IO,_(DIFFIO_RX_B18p,_DIFFOUT_B18p,_DQ3B,_DQ1B)_AD12") (pintype "bidirectional"))
    )
    (net (code "124") (name "/PMOD_A_PIN2_LS") (class "Default")
      (node (ref "IC29") (pin "AE10") (pinfunction "IO,_(DIFFIO_TX_B17p,_DIFFOUT_B17p,_DQ3B,_DQ1B)_AE10") (pintype "bidirectional"))
    )
    (net (code "125") (name "/PMOD_A_PIN3_LS") (class "Default")
      (node (ref "IC29") (pin "AF10") (pinfunction "IO,_(DIFFIO_TX_B17n,_DIFFOUT_B17n)_AF10") (pintype "bidirectional"))
    )
    (net (code "126") (name "/PMOD_A_PIN4_LS") (class "Default")
      (node (ref "IC29") (pin "AD13") (pinfunction "IO,_(DIFFIO_RX_B18n,_DIFFOUT_B18n,_DQ3B,_DQ1B)_AD13") (pintype "bidirectional"))
    )
    (net (code "127") (name "/PMOD_A_PIN7_LS") (class "Default")
      (node (ref "IC29") (pin "AE12") (pinfunction "IO,_(DIFFIO_RX_B22p,_DIFFOUT_B22p,_DQ3B,_DQ1B)_AE12") (pintype "bidirectional"))
    )
    (net (code "128") (name "/PMOD_A_PIN8_LS") (class "Default")
      (node (ref "IC29") (pin "AE13") (pinfunction "IO,_(DIFFIO_RX_B22n,_DIFFOUT_B22n,_DQ3B,_DQ1B)_AE13") (pintype "bidirectional"))
    )
    (net (code "129") (name "/PMOD_A_PIN9_LS") (class "Default")
      (node (ref "IC29") (pin "AJ2") (pinfunction "IO,_(DIFFIO_TX_B20n,_DIFFOUT_B20n,_DQ3B,_DQ1B)_AJ2") (pintype "bidirectional"))
    )
    (net (code "130") (name "/PMOD_A_PIN10_LS") (class "Default")
      (node (ref "IC29") (pin "AJ1") (pinfunction "IO,_(DIFFIO_TX_B20p,_DIFFOUT_B20p)_AJ1") (pintype "bidirectional"))
    )
    (net (code "131") (name "/PMOD_B_PIN1_LS") (class "Default")
      (node (ref "IC29") (pin "AF20") (pinfunction "IO,_(DIFFIO_RX_B74p,_DIFFOUT_B74p,_DQ10B,_DQ3B,_B_DQ_33,_B_DQ_33)_AF20") (pintype "bidirectional"))
    )
    (net (code "132") (name "/PMOD_B_PIN2_LS") (class "Default")
      (node (ref "IC29") (pin "AG21") (pinfunction "IO,_(DIFFIO_RX_B74n,_DIFFOUT_B74n,_DQ10B,_DQ3B,_B_DQ_32,_B_DQ_32)_AG21") (pintype "bidirectional"))
    )
    (net (code "133") (name "/PMOD_B_PIN3_LS") (class "Default")
      (node (ref "IC29") (pin "AF21") (pinfunction "IO,_(DIFFIO_RX_B78p,_DIFFOUT_B78p,_DQ10B,_DQ3B,_B_DQ_37,_B_DQ_37)_AF21") (pintype "bidirectional"))
    )
    (net (code "134") (name "/PMOD_B_PIN4_LS") (class "Default")
      (node (ref "IC29") (pin "AD20") (pinfunction "IO,_(DIFFIO_RX_B75n,_DIFFOUT_B75n,_DQSn10B,_DQSn3B,_B_DQS#_4,_B_DQS#_4)_AD20") (pintype "bidirectional"))
    )
    (net (code "135") (name "/PMOD_B_PIN7_LS") (class "Default")
      (node (ref "IC29") (pin "AK27") (pinfunction "IO,_(DIFFIO_TX_B73p,_DIFFOUT_B73p,_DQ10B,_DQ3B,_B_DQ_34,_B_DQ_34)_AK27") (pintype "bidirectional"))
    )
    (net (code "136") (name "/PMOD_B_PIN8_LS") (class "Default")
      (node (ref "IC29") (pin "AE22") (pinfunction "IO,_(DIFFIO_TX_B77p,_DIFFOUT_B77p,_DQ10B,_DQ3B,_B_DQ_38,_B_DQ_38)_AE22") (pintype "bidirectional"))
    )
    (net (code "137") (name "/PMOD_B_PIN9_LS") (class "Default")
      (node (ref "IC29") (pin "AC21") (pinfunction "IO,_(DIFFIO_RX_B75p,_DIFFOUT_B75p,_DQS10B,_DQS3B,_B_DQS_4,_B_DQS_4)_AC21") (pintype "bidirectional"))
    )
    (net (code "138") (name "/PMOD_B_PIN10_LS") (class "Default")
      (node (ref "IC29") (pin "AH26") (pinfunction "IO,_(DIFFIO_TX_B76n,_DIFFOUT_B76n,_DQ10B,_DQ3B,_B_DQ_35,_B_DQ_35)_AH26") (pintype "bidirectional"))
    )
    (net (code "139") (name "/SI_CLK6") (class "Default")
      (node (ref "IC29") (pin "AB18") (pinfunction "IO,_CLK3n,_(DIFFIO_RX_B55n,_DIFFOUT_B55n)_AB18") (pintype "bidirectional"))
    )
    (net (code "140") (name "/SI_CLK7") (class "Default")
      (node (ref "IC29") (pin "AC15") (pinfunction "IO,_CLK2n,_(DIFFIO_RX_B47n,_DIFFOUT_B47n)_AC15") (pintype "bidirectional"))
    )
    (net (code "141") (name "/SR_DIN_LS") (class "Default")
      (node (ref "IC29") (pin "AJ5") (pinfunction "IO,_(DIFFIO_TX_B24n,_DIFFOUT_B24n,_DQ3B,_DQ1B)_AJ5") (pintype "bidirectional"))
    )
    (net (code "142") (name "/SR_SCLK_LS") (class "Default")
      (node (ref "IC29") (pin "AA13") (pinfunction "IO,_(DIFFIO_RX_B27n,_DIFFOUT_B27n,_DQSn4B,_DQSn1B,_B_CS#_1,_B_CS#_1)_AA13") (pintype "bidirectional"))
    )
    (net (code "143") (name "GND") (class "Default")
      (node (ref "IC29") (pin "AA18") (pinfunction "IO,_(DIFFIO_RX_B63p,_DIFFOUT_B63p,__,__,_GND,_GND)_AA18") (pintype "bidirectional"))
      (node (ref "IC29") (pin "AA19") (pinfunction "IO,_(DIFFIO_RX_B63n,_DIFFOUT_B63n,__,__,_GND,_GND)_AA19") (pintype "bidirectional"))
      (node (ref "IC29") (pin "AA21") (pinfunction "IO,_(DIFFIO_RX_B71p,_DIFFOUT_B71p,__,__,_GND,_GND)_AA21") (pintype "bidirectional"))
      (node (ref "IC29") (pin "AB21") (pinfunction "IO,_(DIFFIO_RX_B71n,_DIFFOUT_B71n,__,__,_GND,_GND)_AB21") (pintype "bidirectional"))
      (node (ref "IC29") (pin "AB22") (pinfunction "IO,_(DIFFIO_RX_B79p,_DIFFOUT_B79p,__,__,_GND,_GND)_AB22") (pintype "bidirectional"))
      (node (ref "IC29") (pin "AC22") (pinfunction "IO,_(DIFFIO_RX_B79n,_DIFFOUT_B79n,__,__,_GND,_GND)_AC22") (pintype "bidirectional"))
      (node (ref "IC29") (pin "AF23") (pinfunction "IO,_(DIFFIO_TX_B77n,_DIFFOUT_B77n,_DQ10B,_DQ3B,_GND,_GND)_AF23") (pintype "bidirectional"))
      (node (ref "IC29") (pin "AG26") (pinfunction "IO,_(DIFFIO_TX_B76p,_DIFFOUT_B76p,__,__,_GND,_GND)_AG26") (pintype "bidirectional"))
      (node (ref "IC29") (pin "AH17") (pinfunction "IO,_(DIFFIO_TX_B49n,_DIFFOUT_B49n,__,__,_GND,_GND)_AH17") (pintype "bidirectional"))
      (node (ref "IC29") (pin "AH25") (pinfunction "IO,_(DIFFIO_TX_B69n,_DIFFOUT_B69n,_DQ9B,_DQ3B,_GND,_GND)_AH25") (pintype "bidirectional"))
      (node (ref "IC29") (pin "AJ22") (pinfunction "IO,_(DIFFIO_TX_B61n,_DIFFOUT_B61n,_DQ8B,_DQ2B,_GND,_GND)_AJ22") (pintype "bidirectional"))
      (node (ref "IC29") (pin "AJ24") (pinfunction "IO,_(DIFFIO_TX_B65n,_DIFFOUT_B65n,__,__,_GND,_GND)_AJ24") (pintype "bidirectional"))
      (node (ref "IC29") (pin "AJ25") (pinfunction "IO,_(DIFFIO_TX_B68p,_DIFFOUT_B68p,__,__,_GND,_GND)_AJ25") (pintype "bidirectional"))
      (node (ref "IC29") (pin "AJ9") (pinfunction "IO,_(DIFFIO_TX_B33n,_DIFFOUT_B33n,__,__,_GND,_GND)_AJ9") (pintype "bidirectional"))
      (node (ref "IC29") (pin "AK20") (pinfunction "IO,_(DIFFIO_TX_B57n,_DIFFOUT_B57n,__,__,_GND,_GND)_AK20") (pintype "bidirectional"))
      (node (ref "IC29") (pin "AK28") (pinfunction "IO,_(DIFFIO_TX_B73n,_DIFFOUT_B73n,__,__,_GND,_GND)_AK28") (pintype "bidirectional"))
      (node (ref "IC29") (pin "AK6") (pinfunction "IO,_(DIFFIO_TX_B25n,_DIFFOUT_B25n,__,__,_GND,_GND)_AK6") (pintype "bidirectional"))
      (node (ref "R154") (pin "1") (pinfunction "1_1") (pintype "passive"))
    )
    (net (code "144") (name "unconnected-(FL3-Pad1)") (class "Default")
      (node (ref "FL3") (pin "1") (pintype "passive+no_connect"))
    )
    (net (code "145") (name "unconnected-(FL4-Pad1)") (class "Default")
      (node (ref "FL4") (pin "1") (pintype "passive+no_connect"))
    )
    (net (code "146") (name "unconnected-(IC29B-IO,_CLK1n,_(DIFFIO_RX_B39n,_DIFFOUT_B39n)-PadAA15)") (class "Default")
      (node (ref "IC29") (pin "AA15") (pinfunction "IO,_CLK1n,_(DIFFIO_RX_B39n,_DIFFOUT_B39n)_AA15") (pintype "bidirectional+no_connect"))
    )
  )
)
